# S4_Power_Supply.net
KiCad netlist of a schematic drawn in Altium Designer
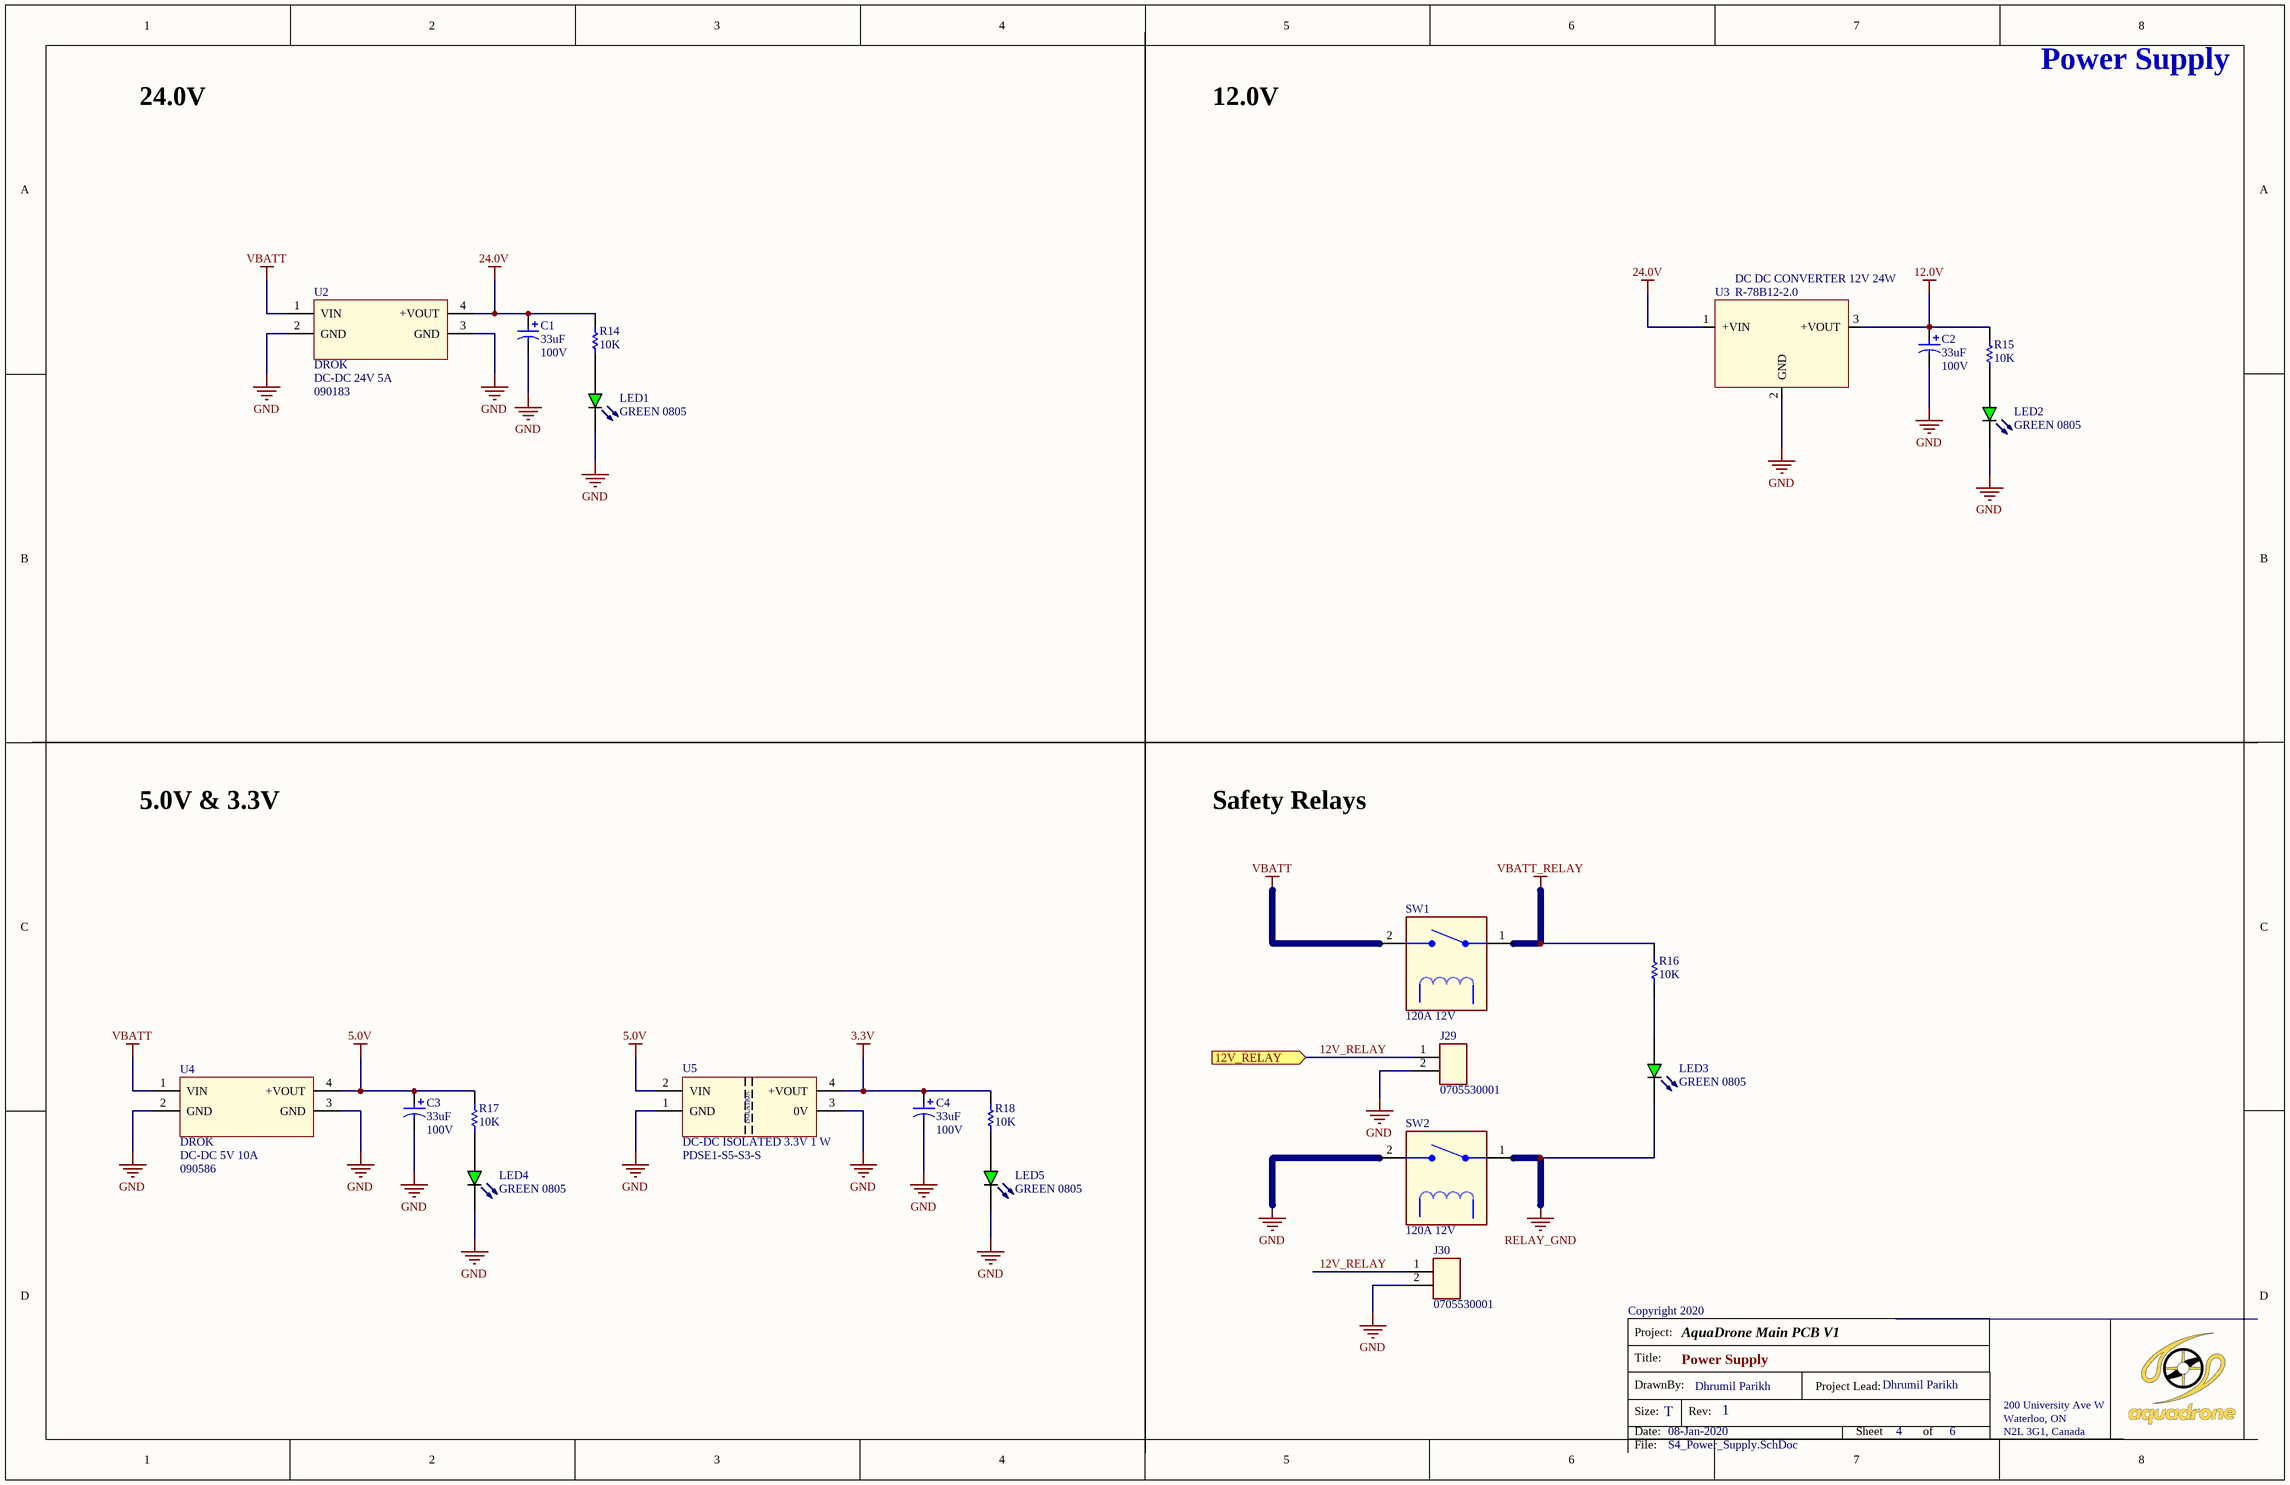
[diagram p0: S4_Power_Supply.SchDoc]

(export (version "E")
  (design (tool "Eeschema 10.0.6"))
  (components
    (comp (ref "C1")
      (value "33uF")
      (footprint "RWMN:CAPPRD350W60D825H1700")
      (description "CAP ALUM 33UF 20% 100V RADIAL")
      (fields
        (field (name "MFG") "Nichicon")
        (field (name "MFG_PART_NO") "UPM2A330MPD1TD")
        (field (name "VOLTAGE") "100V")
      )
      (libsource (lib "AquaDrone") (part "CAP ALUM 33UF 20% 100V RADIAL"))
    )
    (comp (ref "C2")
      (value "33uF")
      (footprint "RWMN:CAPPRD350W60D825H1700")
      (description "CAP ALUM 33UF 20% 100V RADIAL")
      (fields
        (field (name "MFG") "Nichicon")
        (field (name "MFG_PART_NO") "UPM2A330MPD1TD")
        (field (name "VOLTAGE") "100V")
      )
      (libsource (lib "AquaDrone") (part "CAP ALUM 33UF 20% 100V RADIAL"))
    )
    (comp (ref "C3")
      (value "33uF")
      (footprint "RWMN:CAPPRD350W60D825H1700")
      (description "CAP ALUM 33UF 20% 100V RADIAL")
      (fields
        (field (name "MFG") "Nichicon")
        (field (name "MFG_PART_NO") "UPM2A330MPD1TD")
        (field (name "VOLTAGE") "100V")
      )
      (libsource (lib "AquaDrone") (part "CAP ALUM 33UF 20% 100V RADIAL"))
    )
    (comp (ref "C4")
      (value "33uF")
      (footprint "RWMN:CAPPRD350W60D825H1700")
      (description "CAP ALUM 33UF 20% 100V RADIAL")
      (fields
        (field (name "MFG") "Nichicon")
        (field (name "MFG_PART_NO") "UPM2A330MPD1TD")
        (field (name "VOLTAGE") "100V")
      )
      (libsource (lib "AquaDrone") (part "CAP ALUM 33UF 20% 100V RADIAL"))
    )
    (comp (ref "J29")
      (value "0705530001")
      (footprint "SHDRRA2W109P0_254_1X2_762X1359X699P")
      (description "CONN HEADER R/A 2POS 2.54MM")
      (fields (field (name "MFG") "Molex"))
      (libsource (lib "AquaDrone") (part "CONN HEADER R/A 2POS 2.54MM"))
    )
    (comp (ref "J30")
      (value "0705530001")
      (footprint "SHDRRA2W109P0_254_1X2_762X1359X699P")
      (description "CONN HEADER R/A 2POS 2.54MM")
      (fields (field (name "MFG") "Molex"))
      (libsource (lib "AquaDrone") (part "CONN HEADER R/A 2POS 2.54MM"))
    )
    (comp (ref "LED1")
      (value "GREEN 0805")
      (footprint "LED0805")
      (description "LED GREEN CLEAR 0805 SMD")
      (fields (field (name "MFG") "Würth Elektronik") (field (name "MFG_PART_NO") "150080VS75000"))
      (libsource (lib "AquaDrone") (part "LED GREEN CLEAR 0805 SMD"))
    )
    (comp (ref "LED2")
      (value "GREEN 0805")
      (footprint "LED0805")
      (description "LED GREEN CLEAR 0805 SMD")
      (fields (field (name "MFG") "Würth Elektronik") (field (name "MFG_PART_NO") "150080VS75000"))
      (libsource (lib "AquaDrone") (part "LED GREEN CLEAR 0805 SMD"))
    )
    (comp (ref "LED3")
      (value "GREEN 0805")
      (footprint "LED0805")
      (description "LED GREEN CLEAR 0805 SMD")
      (fields (field (name "MFG") "Würth Elektronik") (field (name "MFG_PART_NO") "150080VS75000"))
      (libsource (lib "AquaDrone") (part "LED GREEN CLEAR 0805 SMD"))
    )
    (comp (ref "LED4")
      (value "GREEN 0805")
      (footprint "LED0805")
      (description "LED GREEN CLEAR 0805 SMD")
      (fields (field (name "MFG") "Würth Elektronik") (field (name "MFG_PART_NO") "150080VS75000"))
      (libsource (lib "AquaDrone") (part "LED GREEN CLEAR 0805 SMD"))
    )
    (comp (ref "LED5")
      (value "GREEN 0805")
      (footprint "LED0805")
      (description "LED GREEN CLEAR 0805 SMD")
      (fields (field (name "MFG") "Würth Elektronik") (field (name "MFG_PART_NO") "150080VS75000"))
      (libsource (lib "AquaDrone") (part "LED GREEN CLEAR 0805 SMD"))
    )
    (comp (ref "R14")
      (value "10K")
      (footprint "RESC1608X06N")
      (description "RES SMD 10K OHM 1% 1/10W 0603")
      (fields (field (name "MFG") "Vishay Dale") (field (name "MFG_PART_NO") "CRCW060310K0FKEA"))
      (libsource (lib "AquaDrone") (part "RES SMD 10K OHM 1% 1/10W 0603"))
    )
    (comp (ref "R15")
      (value "10K")
      (footprint "RESC1608X06N")
      (description "RES SMD 10K OHM 1% 1/10W 0603")
      (fields (field (name "MFG") "Vishay Dale") (field (name "MFG_PART_NO") "CRCW060310K0FKEA"))
      (libsource (lib "AquaDrone") (part "RES SMD 10K OHM 1% 1/10W 0603"))
    )
    (comp (ref "R16")
      (value "10K")
      (footprint "RESC1608X06N")
      (description "RES SMD 10K OHM 1% 1/10W 0603")
      (fields (field (name "MFG") "Vishay Dale") (field (name "MFG_PART_NO") "CRCW060310K0FKEA"))
      (libsource (lib "AquaDrone") (part "RES SMD 10K OHM 1% 1/10W 0603"))
    )
    (comp (ref "R17")
      (value "10K")
      (footprint "RESC1608X06N")
      (description "RES SMD 10K OHM 1% 1/10W 0603")
      (fields (field (name "MFG") "Vishay Dale") (field (name "MFG_PART_NO") "CRCW060310K0FKEA"))
      (libsource (lib "AquaDrone") (part "RES SMD 10K OHM 1% 1/10W 0603"))
    )
    (comp (ref "R18")
      (value "10K")
      (footprint "RESC1608X06N")
      (description "RES SMD 10K OHM 1% 1/10W 0603")
      (fields (field (name "MFG") "Vishay Dale") (field (name "MFG_PART_NO") "CRCW060310K0FKEA"))
      (libsource (lib "AquaDrone") (part "RES SMD 10K OHM 1% 1/10W 0603"))
    )
    (comp (ref "SW1")
      (value "120A 12V")
      (footprint "G9TB-U1ATW-E DC12")
      (description "RELAY GEN PURPOSE SPST 120A 12V")
      (fields (field (name "MFG") "Omron") (field (name "MFG_PART_NO") "G9TB-U1ATW-E DC12"))
      (libsource (lib "AquaDrone") (part "RELAY GEN PURPOSE SPST 120A 12V"))
    )
    (comp (ref "SW2")
      (value "120A 12V")
      (footprint "G9TB-U1ATW-E DC12")
      (description "RELAY GEN PURPOSE SPST 120A 12V")
      (fields (field (name "MFG") "Omron") (field (name "MFG_PART_NO") "G9TB-U1ATW-E DC12"))
      (libsource (lib "AquaDrone") (part "RELAY GEN PURPOSE SPST 120A 12V"))
    )
    (comp (ref "U2")
      (value "DC-DC 24V 5A")
      (footprint "DROK 090183 24V 5A")
      (fields (field (name "MFG") "DROK") (field (name "MFG_PART_NO") "090183"))
      (libsource (lib "AquaDrone") (part "DC-DC 24V 5A"))
    )
    (comp (ref "U3")
      (value "DC DC CONVERTER 12V 24W")
      (footprint "R-78B12-2.0")
      (fields (field (name "MFG") "Recom Power") (field (name "MFG_PART_NO") "R-78B12-2.0"))
      (libsource (lib "AquaDrone") (part "DC DC CONVERTER 12V 24W"))
    )
    (comp (ref "U4")
      (value "DC-DC 5V 10A")
      (footprint "DROK 090586 5V 10A")
      (fields (field (name "MFG") "DROK") (field (name "MFG_PART_NO") "090586"))
      (libsource (lib "AquaDrone") (part "DC-DC 5V 10A"))
    )
    (comp (ref "U5")
      (value "DC-DC ISOLATED 3.3V 1 W")
      (footprint "PDSE1S5S3S")
      (fields (field (name "MFG") "CUI Inc.") (field (name "MFG_PART_NO") "PDSE1-S5-S3-S"))
      (libsource (lib "AquaDrone") (part "DC-DC ISOLATED 3.3V 1 W"))
    )
  )
  (nets
    (net (code "1") (name "/12V_RELAY") (class "Default")
      (node (ref "J29") (pin "1") (pintype "passive"))
      (node (ref "J30") (pin "1") (pintype "passive"))
    )
    (net (code "2") (name "3.3V") (class "Default")
      (node (ref "C4") (pin "1") (pinfunction "1_1") (pintype "passive"))
      (node (ref "R18") (pin "2") (pinfunction "2_2") (pintype "passive"))
      (node (ref "U5") (pin "4") (pinfunction "+VOUT_4") (pintype "power_in"))
    )
    (net (code "3") (name "5.0V") (class "Default")
      (node (ref "C3") (pin "1") (pinfunction "1_1") (pintype "passive"))
      (node (ref "R17") (pin "2") (pinfunction "2_2") (pintype "passive"))
      (node (ref "U4") (pin "4") (pinfunction "+VOUT_4") (pintype "power_in"))
      (node (ref "U5") (pin "2") (pinfunction "VIN_2") (pintype "power_in"))
    )
    (net (code "4") (name "12.0V") (class "Default")
      (node (ref "C2") (pin "1") (pinfunction "1_1") (pintype "passive"))
      (node (ref "R15") (pin "2") (pinfunction "2_2") (pintype "passive"))
      (node (ref "U3") (pin "3") (pinfunction "+VOUT_3") (pintype "power_in"))
    )
    (net (code "5") (name "24.0V") (class "Default")
      (node (ref "C1") (pin "1") (pinfunction "1_1") (pintype "passive"))
      (node (ref "R14") (pin "2") (pinfunction "2_2") (pintype "passive"))
      (node (ref "U2") (pin "4") (pinfunction "+VOUT_4") (pintype "power_in"))
      (node (ref "U3") (pin "1") (pinfunction "+VIN_1") (pintype "power_in"))
    )
    (net (code "6") (name "GND") (class "Default")
      (node (ref "C1") (pin "2") (pinfunction "2_2") (pintype "passive"))
      (node (ref "C2") (pin "2") (pinfunction "2_2") (pintype "passive"))
      (node (ref "C3") (pin "2") (pinfunction "2_2") (pintype "passive"))
      (node (ref "C4") (pin "2") (pinfunction "2_2") (pintype "passive"))
      (node (ref "J29") (pin "2") (pintype "passive"))
      (node (ref "J30") (pin "2") (pintype "passive"))
      (node (ref "LED1") (pin "K") (pinfunction "K_K") (pintype "passive"))
      (node (ref "LED2") (pin "K") (pinfunction "K_K") (pintype "passive"))
      (node (ref "LED4") (pin "K") (pinfunction "K_K") (pintype "passive"))
      (node (ref "LED5") (pin "K") (pinfunction "K_K") (pintype "passive"))
      (node (ref "SW2") (pin "2") (pintype "power_in"))
      (node (ref "U2") (pin "2") (pinfunction "GND_2") (pintype "power_in"))
      (node (ref "U2") (pin "3") (pinfunction "GND_3") (pintype "power_in"))
      (node (ref "U3") (pin "2") (pinfunction "GND_2") (pintype "power_in"))
      (node (ref "U4") (pin "2") (pinfunction "GND_2") (pintype "power_in"))
      (node (ref "U4") (pin "3") (pinfunction "GND_3") (pintype "power_in"))
      (node (ref "U5") (pin "1") (pinfunction "GND_1") (pintype "power_in"))
      (node (ref "U5") (pin "3") (pinfunction "0V_3") (pintype "power_in"))
    )
    (net (code "7") (name "Net-(LED1-PadA)") (class "Default")
      (node (ref "LED1") (pin "A") (pinfunction "A_A") (pintype "passive"))
      (node (ref "R14") (pin "1") (pinfunction "1_1") (pintype "passive"))
    )
    (net (code "8") (name "Net-(LED2-PadA)") (class "Default")
      (node (ref "LED2") (pin "A") (pinfunction "A_A") (pintype "passive"))
      (node (ref "R15") (pin "1") (pinfunction "1_1") (pintype "passive"))
    )
    (net (code "9") (name "Net-(LED3-PadA)") (class "Default")
      (node (ref "LED3") (pin "A") (pinfunction "A_A") (pintype "passive"))
      (node (ref "R16") (pin "1") (pinfunction "1_1") (pintype "passive"))
    )
    (net (code "10") (name "Net-(LED4-PadA)") (class "Default")
      (node (ref "LED4") (pin "A") (pinfunction "A_A") (pintype "passive"))
      (node (ref "R17") (pin "1") (pinfunction "1_1") (pintype "passive"))
    )
    (net (code "11") (name "Net-(LED5-PadA)") (class "Default")
      (node (ref "LED5") (pin "A") (pinfunction "A_A") (pintype "passive"))
      (node (ref "R18") (pin "1") (pinfunction "1_1") (pintype "passive"))
    )
    (net (code "12") (name "RELAY_GND") (class "Default")
      (node (ref "LED3") (pin "K") (pinfunction "K_K") (pintype "passive"))
      (node (ref "SW2") (pin "1") (pintype "power_in"))
    )
    (net (code "13") (name "VBATT") (class "Default")
      (node (ref "SW1") (pin "2") (pintype "power_in"))
      (node (ref "U2") (pin "1") (pinfunction "VIN_1") (pintype "power_in"))
      (node (ref "U4") (pin "1") (pinfunction "VIN_1") (pintype "power_in"))
    )
    (net (code "14") (name "VBATT_RELAY") (class "Default")
      (node (ref "R16") (pin "2") (pinfunction "2_2") (pintype "passive"))
      (node (ref "SW1") (pin "1") (pintype "power_in"))
    )
  )
)
